# Measurment_ICs.net
KiCad netlist of a schematic drawn in Altium Designer
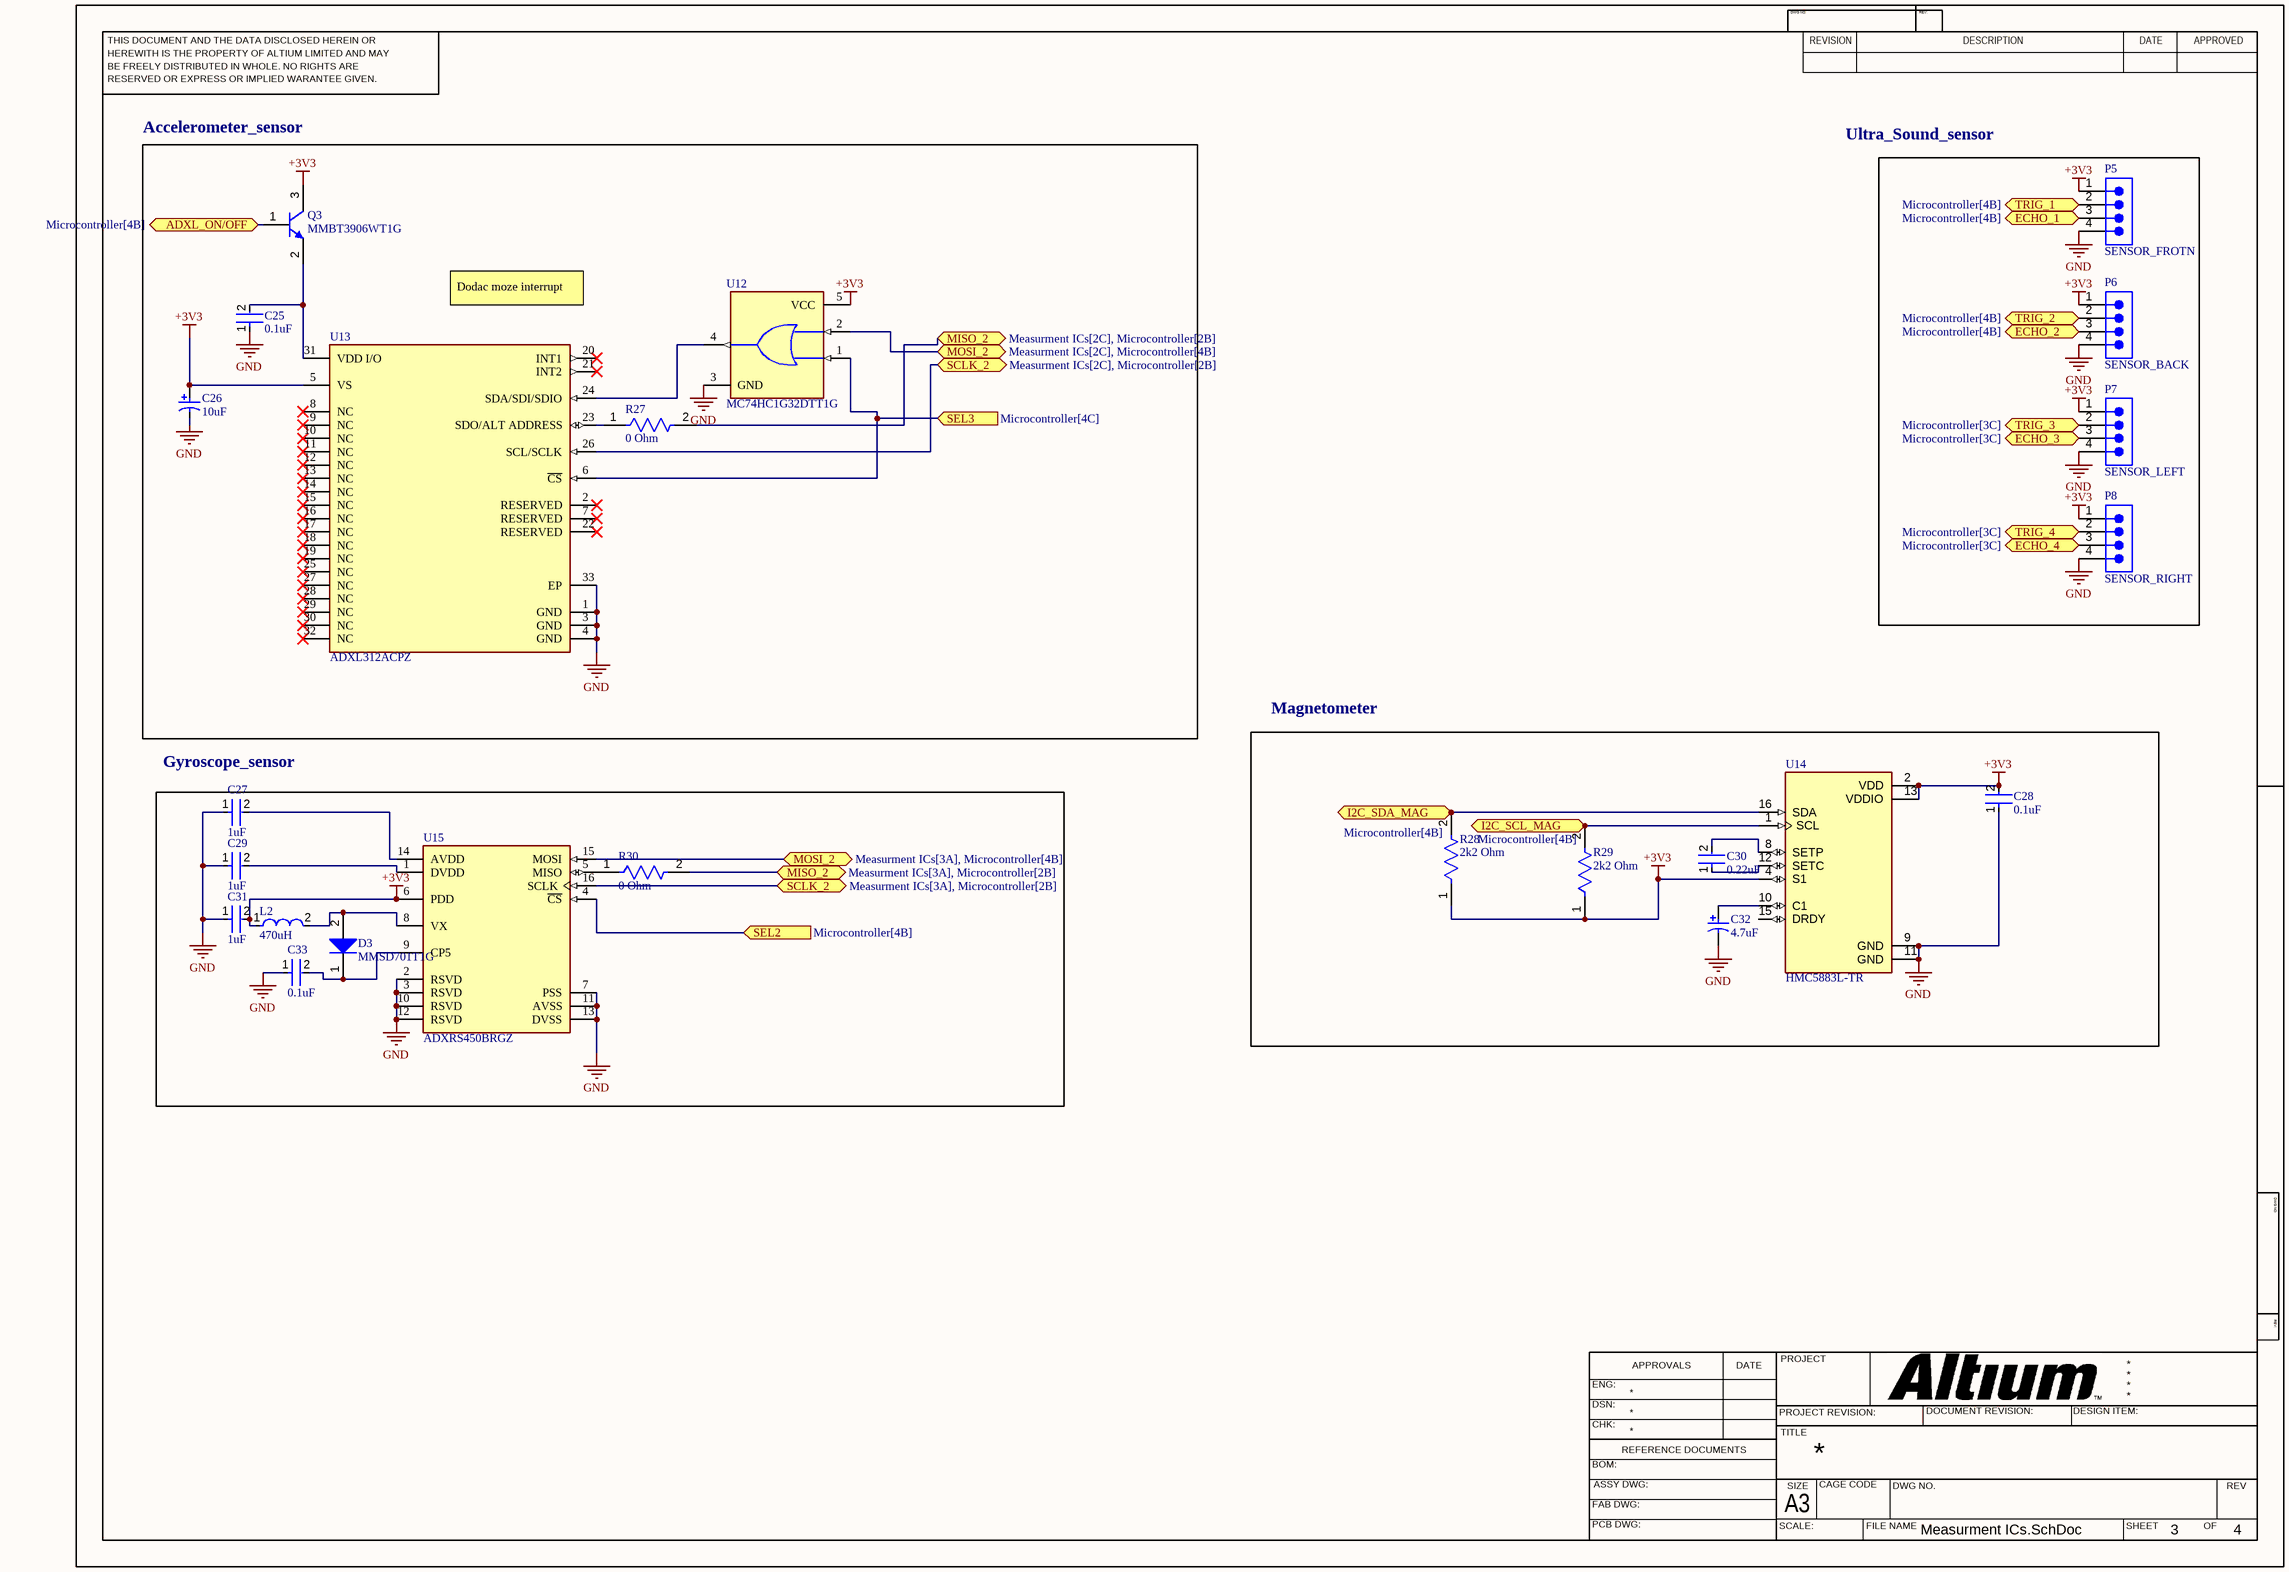
[diagram p0: Measurment ICs.SchDoc]

(export (version "E")
  (design (tool "Eeschema 10.0.6"))
  (components
    (comp (ref "C25")
      (value "0.1uF")
      (footprint "FP-CC0805-0_85-MFG")
      (description "CAP CER 0.1UF 50V X7R 0805")
      (fields (field (name "TOLERANCE") "0.1") (field (name "MANUFACTURER PART NUMBER") "CC0805KRX7R9BB104"))
      (libsource (lib "Altium Content Vault") (part "11868f565c42a9108669ba33697ecf6"))
    )
    (comp (ref "C26")
      (value "10uF")
      (footprint "KEMT-A-3216-18-2_M")
      (description "Capacitor, Tantalum, 10 uF, +/- 10%, 10 V, -55 to 125 degC, 2-Pin SMD (1206), RoHS, Tape and Reel")
      (fields (field (name "TOLERANCE") "±10%") (field (name "MANUFACTURER") "Kemet"))
      (libsource (lib "Altium Content Vault") (part "CAP-P-2"))
    )
    (comp (ref "C27")
      (value "1uF")
      (footprint "FP-CC0805-0_85-MFG")
      (description "CAP CER 0.1UF 50V X7R 0805")
      (fields (field (name "TOLERANCE") "0.1") (field (name "MANUFACTURER PART NUMBER") "CC0805KRX7R9BB104"))
      (libsource (lib "Altium Content Vault") (part "11868f565c42a9108669ba33697ecf6"))
    )
    (comp (ref "C28")
      (value "0.1uF")
      (footprint "FP-CC0805-0_85-MFG")
      (description "CAP CER 0.1UF 50V X7R 0805")
      (fields (field (name "TOLERANCE") "0.1") (field (name "MANUFACTURER PART NUMBER") "CC0805KRX7R9BB104"))
      (libsource (lib "Altium Content Vault") (part "11868f565c42a9108669ba33697ecf6"))
    )
    (comp (ref "C29")
      (value "1uF")
      (footprint "FP-CC0805-0_85-MFG")
      (description "CAP CER 0.1UF 50V X7R 0805")
      (fields (field (name "TOLERANCE") "0.1") (field (name "MANUFACTURER PART NUMBER") "CC0805KRX7R9BB104"))
      (libsource (lib "Altium Content Vault") (part "11868f565c42a9108669ba33697ecf6"))
    )
    (comp (ref "C30")
      (value "0.22uF")
      (footprint "FP-CC0805-0_85-MFG")
      (description "CAP CER 0.1UF 50V X7R 0805")
      (fields (field (name "TOLERANCE") "0.1") (field (name "MANUFACTURER PART NUMBER") "CC0805KRX7R9BB104"))
      (libsource (lib "Altium Content Vault") (part "11868f565c42a9108669ba33697ecf6"))
    )
    (comp (ref "C31")
      (value "1uF")
      (footprint "FP-CC0805-0_85-MFG")
      (description "CAP CER 0.1UF 50V X7R 0805")
      (fields (field (name "TOLERANCE") "0.1") (field (name "MANUFACTURER PART NUMBER") "CC0805KRX7R9BB104"))
      (libsource (lib "Altium Content Vault") (part "11868f565c42a9108669ba33697ecf6"))
    )
    (comp (ref "C32")
      (value "4.7uF")
      (footprint "PNSC-FK-V-D8_V")
      (fields (field (name "MANUFACTURER") "Panasonic"))
      (libsource (lib "Altium Content Vault") (part "CAP-P-2"))
    )
    (comp (ref "C33")
      (value "0.1uF")
      (footprint "FP-CC0805-0_85-MFG")
      (description "CAP CER 0.1UF 50V X7R 0805")
      (fields (field (name "TOLERANCE") "0.1") (field (name "MANUFACTURER PART NUMBER") "CC0805KRX7R9BB104"))
      (libsource (lib "Altium Content Vault") (part "11868f565c42a9108669ba33697ecf6"))
    )
    (comp (ref "D3")
      (value "MMSD701T1G")
      (footprint "ONSC-SOD-123-2-425-04_V")
      (description "Schottky Barrier Diode, 2-Pin SOD-123, Pb-Free, Tape and Reel")
      (fields (field (name "MANUFACTURER") "On Semiconductor"))
      (libsource (lib "Altium Content Vault") (part "ONSC-D-K1A2-2"))
    )
    (comp (ref "L2")
      (value "470uH")
      (footprint "FP-CB2518-MFG")
      (description "SMD Inductors 470uH ±20% 0.07A 28.6Ω 1007")
      (fields (field (name "TOLERANCE") "20%"))
      (libsource (lib "Altium Content Vault") (part "725321dda6339637d4d059423bc1c3c"))
    )
    (comp (ref "P5")
      (value "SENSOR_FROTN")
      (footprint "61300411121")
      (libsource (lib "Altium Content Vault") (part "Header_Male_1R_04P"))
    )
    (comp (ref "P6")
      (value "SENSOR_BACK")
      (footprint "61300411121")
      (libsource (lib "Altium Content Vault") (part "Header_Male_1R_04P"))
    )
    (comp (ref "P7")
      (value "SENSOR_LEFT")
      (footprint "61300411121")
      (libsource (lib "Altium Content Vault") (part "Header_Male_1R_04P"))
    )
    (comp (ref "P8")
      (value "SENSOR_RIGHT")
      (footprint "61300411121")
      (libsource (lib "Altium Content Vault") (part "Header_Male_1R_04P"))
    )
    (comp (ref "Q3")
      (value "MMBT3906WT1G")
      (footprint "ONSC-SC-70-3-419-04_V")
      (description "General Purpose Transistor, PNP Silicon, 3-Pin SC70, Pb-Free, Tape and Reel")
      (fields (field (name "MANUFACTURER") "On Semiconductor"))
      (libsource (lib "Altium Content Vault") (part "ONSC-NPN-B1E2C3-3"))
    )
    (comp (ref "R27")
      (value "0 Ohm")
      (footprint "FP-RMCF0805-MFG")
      (description "RES 0 OHM JUMPER 1/8W 0805")
      (libsource (lib "Altium Content Vault") (part "1029c3af85768c4190bb7ad29bc67b5"))
    )
    (comp (ref "R28")
      (value "2k2 Ohm")
      (footprint "FP-RMCF0805-MFG")
      (description "RES 0 OHM JUMPER 1/8W 0805")
      (libsource (lib "Altium Content Vault") (part "1029c3af85768c4190bb7ad29bc67b5"))
    )
    (comp (ref "R29")
      (value "2k2 Ohm")
      (footprint "FP-RMCF0805-MFG")
      (description "RES 0 OHM JUMPER 1/8W 0805")
      (libsource (lib "Altium Content Vault") (part "1029c3af85768c4190bb7ad29bc67b5"))
    )
    (comp (ref "R30")
      (value "0 Ohm")
      (footprint "FP-RMCF0805-MFG")
      (description "RES 0 OHM JUMPER 1/8W 0805")
      (libsource (lib "Altium Content Vault") (part "1029c3af85768c4190bb7ad29bc67b5"))
    )
    (comp (ref "U12")
      (value "MC74HC1G32DTT1G")
      (footprint "FP-483-MFG")
      (description "MC74HC1G32DTT1G MC74HC Series 4 V Surface Mount Single 2-Input OR Gate - TSOP-5")
      (libsource (lib "Altium Content Vault") (part "7dc5fb894309747e1da8625ad87dccb"))
    )
    (comp (ref "U13")
      (value "ADXL312ACPZ")
      (footprint "FP-CP-32-17-MFG")
      (description "ACCEL 1.5-12G I2C/SPI 32LFCSP")
      (libsource (lib "Altium Content Vault") (part "7523e9a6801b99f6cbf95d05348c854"))
    )
    (comp (ref "U14")
      (value "HMC5883L-TR")
      (footprint "XDCR_HMC5883L-TR")
      (fields (field (name "MF") "STMicroelectronics") (field (name "MP") "HMC5883LTR"))
      (libsource (lib "HMC5883L-TR") (part "HMC5883L-TR"))
    )
    (comp (ref "U15")
      (value "ADXRS450BRGZ")
      (footprint "FP-RG-16-1-IPC_C")
      (description "SENS GYRO 300DEG/S DGTL 16SOIC")
      (libsource (lib "Altium Content Vault") (part "bc2adaa03a4e25db86aafbb646e1801"))
    )
  )
  (nets
    (net (code "1") (name "+3V3") (class "Default")
      (node (ref "C26") (pin "1") (pinfunction "1_1") (pintype "passive"))
      (node (ref "C28") (pin "2") (pinfunction "2_2") (pintype "passive"))
      (node (ref "C31") (pin "2") (pinfunction "2_2") (pintype "passive"))
      (node (ref "L2") (pin "1") (pinfunction "1_1") (pintype "passive"))
      (node (ref "P5") (pin "1") (pinfunction "1_1") (pintype "passive"))
      (node (ref "P6") (pin "1") (pinfunction "1_1") (pintype "passive"))
      (node (ref "P7") (pin "1") (pinfunction "1_1") (pintype "passive"))
      (node (ref "P8") (pin "1") (pinfunction "1_1") (pintype "passive"))
      (node (ref "Q3") (pin "3") (pinfunction "C_3") (pintype "passive"))
      (node (ref "R28") (pin "1") (pinfunction "1_1") (pintype "passive"))
      (node (ref "R29") (pin "1") (pinfunction "1_1") (pintype "passive"))
      (node (ref "U12") (pin "5") (pinfunction "VCC_5") (pintype "power_in"))
      (node (ref "U13") (pin "5") (pinfunction "VS_5") (pintype "power_in"))
      (node (ref "U14") (pin "13") (pinfunction "VDDIO_13") (pintype "power_in"))
      (node (ref "U14") (pin "2") (pinfunction "VDD_2") (pintype "power_in"))
      (node (ref "U14") (pin "4") (pinfunction "S1_4") (pintype "bidirectional"))
      (node (ref "U15") (pin "6") (pinfunction "PDD_6") (pintype "power_in"))
    )
    (net (code "2") (name "/ADXL_ON{slash}OFF") (class "Default")
      (node (ref "Q3") (pin "1") (pinfunction "B_1") (pintype "passive"))
    )
    (net (code "3") (name "/ECHO_1") (class "Default")
      (node (ref "P5") (pin "3") (pinfunction "3_3") (pintype "passive"))
    )
    (net (code "4") (name "/ECHO_2") (class "Default")
      (node (ref "P6") (pin "3") (pinfunction "3_3") (pintype "passive"))
    )
    (net (code "5") (name "/ECHO_3") (class "Default")
      (node (ref "P7") (pin "3") (pinfunction "3_3") (pintype "passive"))
    )
    (net (code "6") (name "/ECHO_4") (class "Default")
      (node (ref "P8") (pin "3") (pinfunction "3_3") (pintype "passive"))
    )
    (net (code "7") (name "/I2C_SCL_MAG") (class "Default")
      (node (ref "R29") (pin "2") (pinfunction "2_2") (pintype "passive"))
      (node (ref "U14") (pin "1") (pinfunction "SCL_1") (pintype "input"))
    )
    (net (code "8") (name "/I2C_SDA_MAG") (class "Default")
      (node (ref "R28") (pin "2") (pinfunction "2_2") (pintype "passive"))
      (node (ref "U14") (pin "16") (pinfunction "SDA_16") (pintype "input"))
    )
    (net (code "9") (name "/MISO_2") (class "Default")
      (node (ref "R27") (pin "2") (pinfunction "2_2") (pintype "passive"))
      (node (ref "R30") (pin "2") (pinfunction "2_2") (pintype "passive"))
    )
    (net (code "10") (name "/MOSI_2") (class "Default")
      (node (ref "U12") (pin "2") (pinfunction "A_2") (pintype "input"))
      (node (ref "U15") (pin "15") (pinfunction "MOSI_15") (pintype "input"))
    )
    (net (code "11") (name "/SCLK_2") (class "Default")
      (node (ref "U13") (pin "26") (pinfunction "SCL/SCLK_26") (pintype "input"))
      (node (ref "U15") (pin "16") (pinfunction "SCLK_16") (pintype "input"))
    )
    (net (code "12") (name "/SEL2") (class "Default")
      (node (ref "U15") (pin "4") (pinfunction "~{CS}_4") (pintype "input"))
    )
    (net (code "13") (name "/SEL3") (class "Default")
      (node (ref "U12") (pin "1") (pinfunction "B_1") (pintype "input"))
      (node (ref "U13") (pin "6") (pinfunction "~{CS}_6") (pintype "input"))
    )
    (net (code "14") (name "/TRIG_1") (class "Default")
      (node (ref "P5") (pin "2") (pinfunction "2_2") (pintype "passive"))
    )
    (net (code "15") (name "/TRIG_2") (class "Default")
      (node (ref "P6") (pin "2") (pinfunction "2_2") (pintype "passive"))
    )
    (net (code "16") (name "/TRIG_3") (class "Default")
      (node (ref "P7") (pin "2") (pinfunction "2_2") (pintype "passive"))
    )
    (net (code "17") (name "/TRIG_4") (class "Default")
      (node (ref "P8") (pin "2") (pinfunction "2_2") (pintype "passive"))
    )
    (net (code "18") (name "GND") (class "Default")
      (node (ref "C25") (pin "1") (pinfunction "1_1") (pintype "passive"))
      (node (ref "C26") (pin "2") (pinfunction "2_2") (pintype "passive"))
      (node (ref "C27") (pin "1") (pinfunction "1_1") (pintype "passive"))
      (node (ref "C28") (pin "1") (pinfunction "1_1") (pintype "passive"))
      (node (ref "C29") (pin "1") (pinfunction "1_1") (pintype "passive"))
      (node (ref "C31") (pin "1") (pinfunction "1_1") (pintype "passive"))
      (node (ref "C32") (pin "2") (pinfunction "2_2") (pintype "passive"))
      (node (ref "C33") (pin "1") (pinfunction "1_1") (pintype "passive"))
      (node (ref "P5") (pin "4") (pinfunction "4_4") (pintype "passive"))
      (node (ref "P6") (pin "4") (pinfunction "4_4") (pintype "passive"))
      (node (ref "P7") (pin "4") (pinfunction "4_4") (pintype "passive"))
      (node (ref "P8") (pin "4") (pinfunction "4_4") (pintype "passive"))
      (node (ref "U12") (pin "3") (pinfunction "GND_3") (pintype "power_in"))
      (node (ref "U13") (pin "1") (pinfunction "GND_1") (pintype "power_in"))
      (node (ref "U13") (pin "3") (pinfunction "GND_3") (pintype "power_in"))
      (node (ref "U13") (pin "33") (pinfunction "EP_33") (pintype "power_in"))
      (node (ref "U13") (pin "4") (pinfunction "GND_4") (pintype "power_in"))
      (node (ref "U14") (pin "11") (pinfunction "GND_11") (pintype "power_in"))
      (node (ref "U14") (pin "9") (pinfunction "GND_9") (pintype "power_in"))
      (node (ref "U15") (pin "10") (pinfunction "RSVD_10") (pintype "power_in"))
      (node (ref "U15") (pin "11") (pinfunction "AVSS_11") (pintype "power_in"))
      (node (ref "U15") (pin "12") (pinfunction "RSVD_12") (pintype "power_in"))
      (node (ref "U15") (pin "13") (pinfunction "DVSS_13") (pintype "power_in"))
      (node (ref "U15") (pin "2") (pinfunction "RSVD_2") (pintype "power_in"))
      (node (ref "U15") (pin "3") (pinfunction "RSVD_3") (pintype "power_in"))
      (node (ref "U15") (pin "7") (pinfunction "PSS_7") (pintype "power_in"))
    )
    (net (code "19") (name "Net-(D3-A)") (class "Default")
      (node (ref "D3") (pin "2") (pinfunction "A_2") (pintype "passive"))
      (node (ref "L2") (pin "2") (pinfunction "2_2") (pintype "passive"))
      (node (ref "U15") (pin "8") (pinfunction "VX_8") (pintype "power_in"))
    )
    (net (code "20") (name "Net-(D3-K)") (class "Default")
      (node (ref "C33") (pin "2") (pinfunction "2_2") (pintype "passive"))
      (node (ref "D3") (pin "1") (pinfunction "K_1") (pintype "passive"))
      (node (ref "U15") (pin "9") (pinfunction "CP5_9") (pintype "power_in"))
    )
    (net (code "21") (name "Net-(Q3-E)") (class "Default")
      (node (ref "C25") (pin "2") (pinfunction "2_2") (pintype "passive"))
      (node (ref "Q3") (pin "2") (pinfunction "E_2") (pintype "passive"))
      (node (ref "U13") (pin "31") (pinfunction "VDD_I/O_31") (pintype "power_in"))
    )
    (net (code "22") (name "Net-(U12-Y)") (class "Default")
      (node (ref "U12") (pin "4") (pinfunction "Y_4") (pintype "output"))
      (node (ref "U13") (pin "24") (pinfunction "SDA/SDI/SDIO_24") (pintype "input"))
    )
    (net (code "23") (name "Net-(U13-SDO{slash}ALT_ADDRESS)") (class "Default")
      (node (ref "R27") (pin "1") (pinfunction "1_1") (pintype "passive"))
      (node (ref "U13") (pin "23") (pinfunction "SDO/ALT_ADDRESS_23") (pintype "bidirectional"))
    )
    (net (code "24") (name "Net-(U14-C1)") (class "Default")
      (node (ref "C32") (pin "1") (pinfunction "1_1") (pintype "passive"))
      (node (ref "U14") (pin "10") (pinfunction "C1_10") (pintype "bidirectional"))
    )
    (net (code "25") (name "Net-(U14-SETC)") (class "Default")
      (node (ref "C30") (pin "1") (pinfunction "1_1") (pintype "passive"))
      (node (ref "U14") (pin "12") (pinfunction "SETC_12") (pintype "bidirectional"))
    )
    (net (code "26") (name "Net-(U14-SETP)") (class "Default")
      (node (ref "C30") (pin "2") (pinfunction "2_2") (pintype "passive"))
      (node (ref "U14") (pin "8") (pinfunction "SETP_8") (pintype "bidirectional"))
    )
    (net (code "27") (name "Net-(U15-AVDD)") (class "Default")
      (node (ref "C27") (pin "2") (pinfunction "2_2") (pintype "passive"))
      (node (ref "U15") (pin "14") (pinfunction "AVDD_14") (pintype "power_in"))
    )
    (net (code "28") (name "Net-(U15-DVDD)") (class "Default")
      (node (ref "C29") (pin "2") (pinfunction "2_2") (pintype "passive"))
      (node (ref "U15") (pin "1") (pinfunction "DVDD_1") (pintype "power_in"))
    )
    (net (code "29") (name "Net-(U15-MISO)") (class "Default")
      (node (ref "R30") (pin "1") (pinfunction "1_1") (pintype "passive"))
      (node (ref "U15") (pin "5") (pinfunction "MISO_5") (pintype "bidirectional"))
    )
    (net (code "30") (name "unconnected-(U13-INT1-Pad20)") (class "Default")
      (node (ref "U13") (pin "20") (pinfunction "INT1_20") (pintype "output+no_connect"))
    )
    (net (code "31") (name "unconnected-(U13-INT2-Pad21)") (class "Default")
      (node (ref "U13") (pin "21") (pinfunction "INT2_21") (pintype "output+no_connect"))
    )
    (net (code "32") (name "unconnected-(U13-NC-Pad8)") (class "Default")
      (node (ref "U13") (pin "8") (pinfunction "NC_8") (pintype "passive+no_connect"))
    )
    (net (code "33") (name "unconnected-(U13-NC-Pad9)") (class "Default")
      (node (ref "U13") (pin "9") (pinfunction "NC_9") (pintype "passive+no_connect"))
    )
    (net (code "34") (name "unconnected-(U13-NC-Pad10)") (class "Default")
      (node (ref "U13") (pin "10") (pinfunction "NC_10") (pintype "passive+no_connect"))
    )
    (net (code "35") (name "unconnected-(U13-NC-Pad11)") (class "Default")
      (node (ref "U13") (pin "11") (pinfunction "NC_11") (pintype "passive+no_connect"))
    )
    (net (code "36") (name "unconnected-(U13-NC-Pad12)") (class "Default")
      (node (ref "U13") (pin "12") (pinfunction "NC_12") (pintype "passive+no_connect"))
    )
    (net (code "37") (name "unconnected-(U13-NC-Pad13)") (class "Default")
      (node (ref "U13") (pin "13") (pinfunction "NC_13") (pintype "passive+no_connect"))
    )
    (net (code "38") (name "unconnected-(U13-NC-Pad14)") (class "Default")
      (node (ref "U13") (pin "14") (pinfunction "NC_14") (pintype "passive+no_connect"))
    )
    (net (code "39") (name "unconnected-(U13-NC-Pad15)") (class "Default")
      (node (ref "U13") (pin "15") (pinfunction "NC_15") (pintype "passive+no_connect"))
    )
    (net (code "40") (name "unconnected-(U13-NC-Pad16)") (class "Default")
      (node (ref "U13") (pin "16") (pinfunction "NC_16") (pintype "passive+no_connect"))
    )
    (net (code "41") (name "unconnected-(U13-NC-Pad17)") (class "Default")
      (node (ref "U13") (pin "17") (pinfunction "NC_17") (pintype "passive+no_connect"))
    )
    (net (code "42") (name "unconnected-(U13-NC-Pad18)") (class "Default")
      (node (ref "U13") (pin "18") (pinfunction "NC_18") (pintype "passive+no_connect"))
    )
    (net (code "43") (name "unconnected-(U13-NC-Pad19)") (class "Default")
      (node (ref "U13") (pin "19") (pinfunction "NC_19") (pintype "passive+no_connect"))
    )
    (net (code "44") (name "unconnected-(U13-NC-Pad25)") (class "Default")
      (node (ref "U13") (pin "25") (pinfunction "NC_25") (pintype "passive+no_connect"))
    )
    (net (code "45") (name "unconnected-(U13-NC-Pad27)") (class "Default")
      (node (ref "U13") (pin "27") (pinfunction "NC_27") (pintype "passive+no_connect"))
    )
    (net (code "46") (name "unconnected-(U13-NC-Pad28)") (class "Default")
      (node (ref "U13") (pin "28") (pinfunction "NC_28") (pintype "passive+no_connect"))
    )
    (net (code "47") (name "unconnected-(U13-NC-Pad29)") (class "Default")
      (node (ref "U13") (pin "29") (pinfunction "NC_29") (pintype "passive+no_connect"))
    )
    (net (code "48") (name "unconnected-(U13-NC-Pad30)") (class "Default")
      (node (ref "U13") (pin "30") (pinfunction "NC_30") (pintype "passive+no_connect"))
    )
    (net (code "49") (name "unconnected-(U13-NC-Pad32)") (class "Default")
      (node (ref "U13") (pin "32") (pinfunction "NC_32") (pintype "passive+no_connect"))
    )
    (net (code "50") (name "unconnected-(U13-RESERVED-Pad2)") (class "Default")
      (node (ref "U13") (pin "2") (pinfunction "RESERVED_2") (pintype "passive+no_connect"))
    )
    (net (code "51") (name "unconnected-(U13-RESERVED-Pad7)") (class "Default")
      (node (ref "U13") (pin "7") (pinfunction "RESERVED_7") (pintype "passive+no_connect"))
    )
    (net (code "52") (name "unconnected-(U13-RESERVED-Pad22)") (class "Default")
      (node (ref "U13") (pin "22") (pinfunction "RESERVED_22") (pintype "passive+no_connect"))
    )
    (net (code "53") (name "unconnected-(U14-DRDY-Pad15)") (class "Default")
      (node (ref "U14") (pin "15") (pinfunction "DRDY_15") (pintype "bidirectional"))
    )
  )
)
